# GD32Fx07R-dev-board.net
KiCad netlist of a schematic drawn in EAGLE
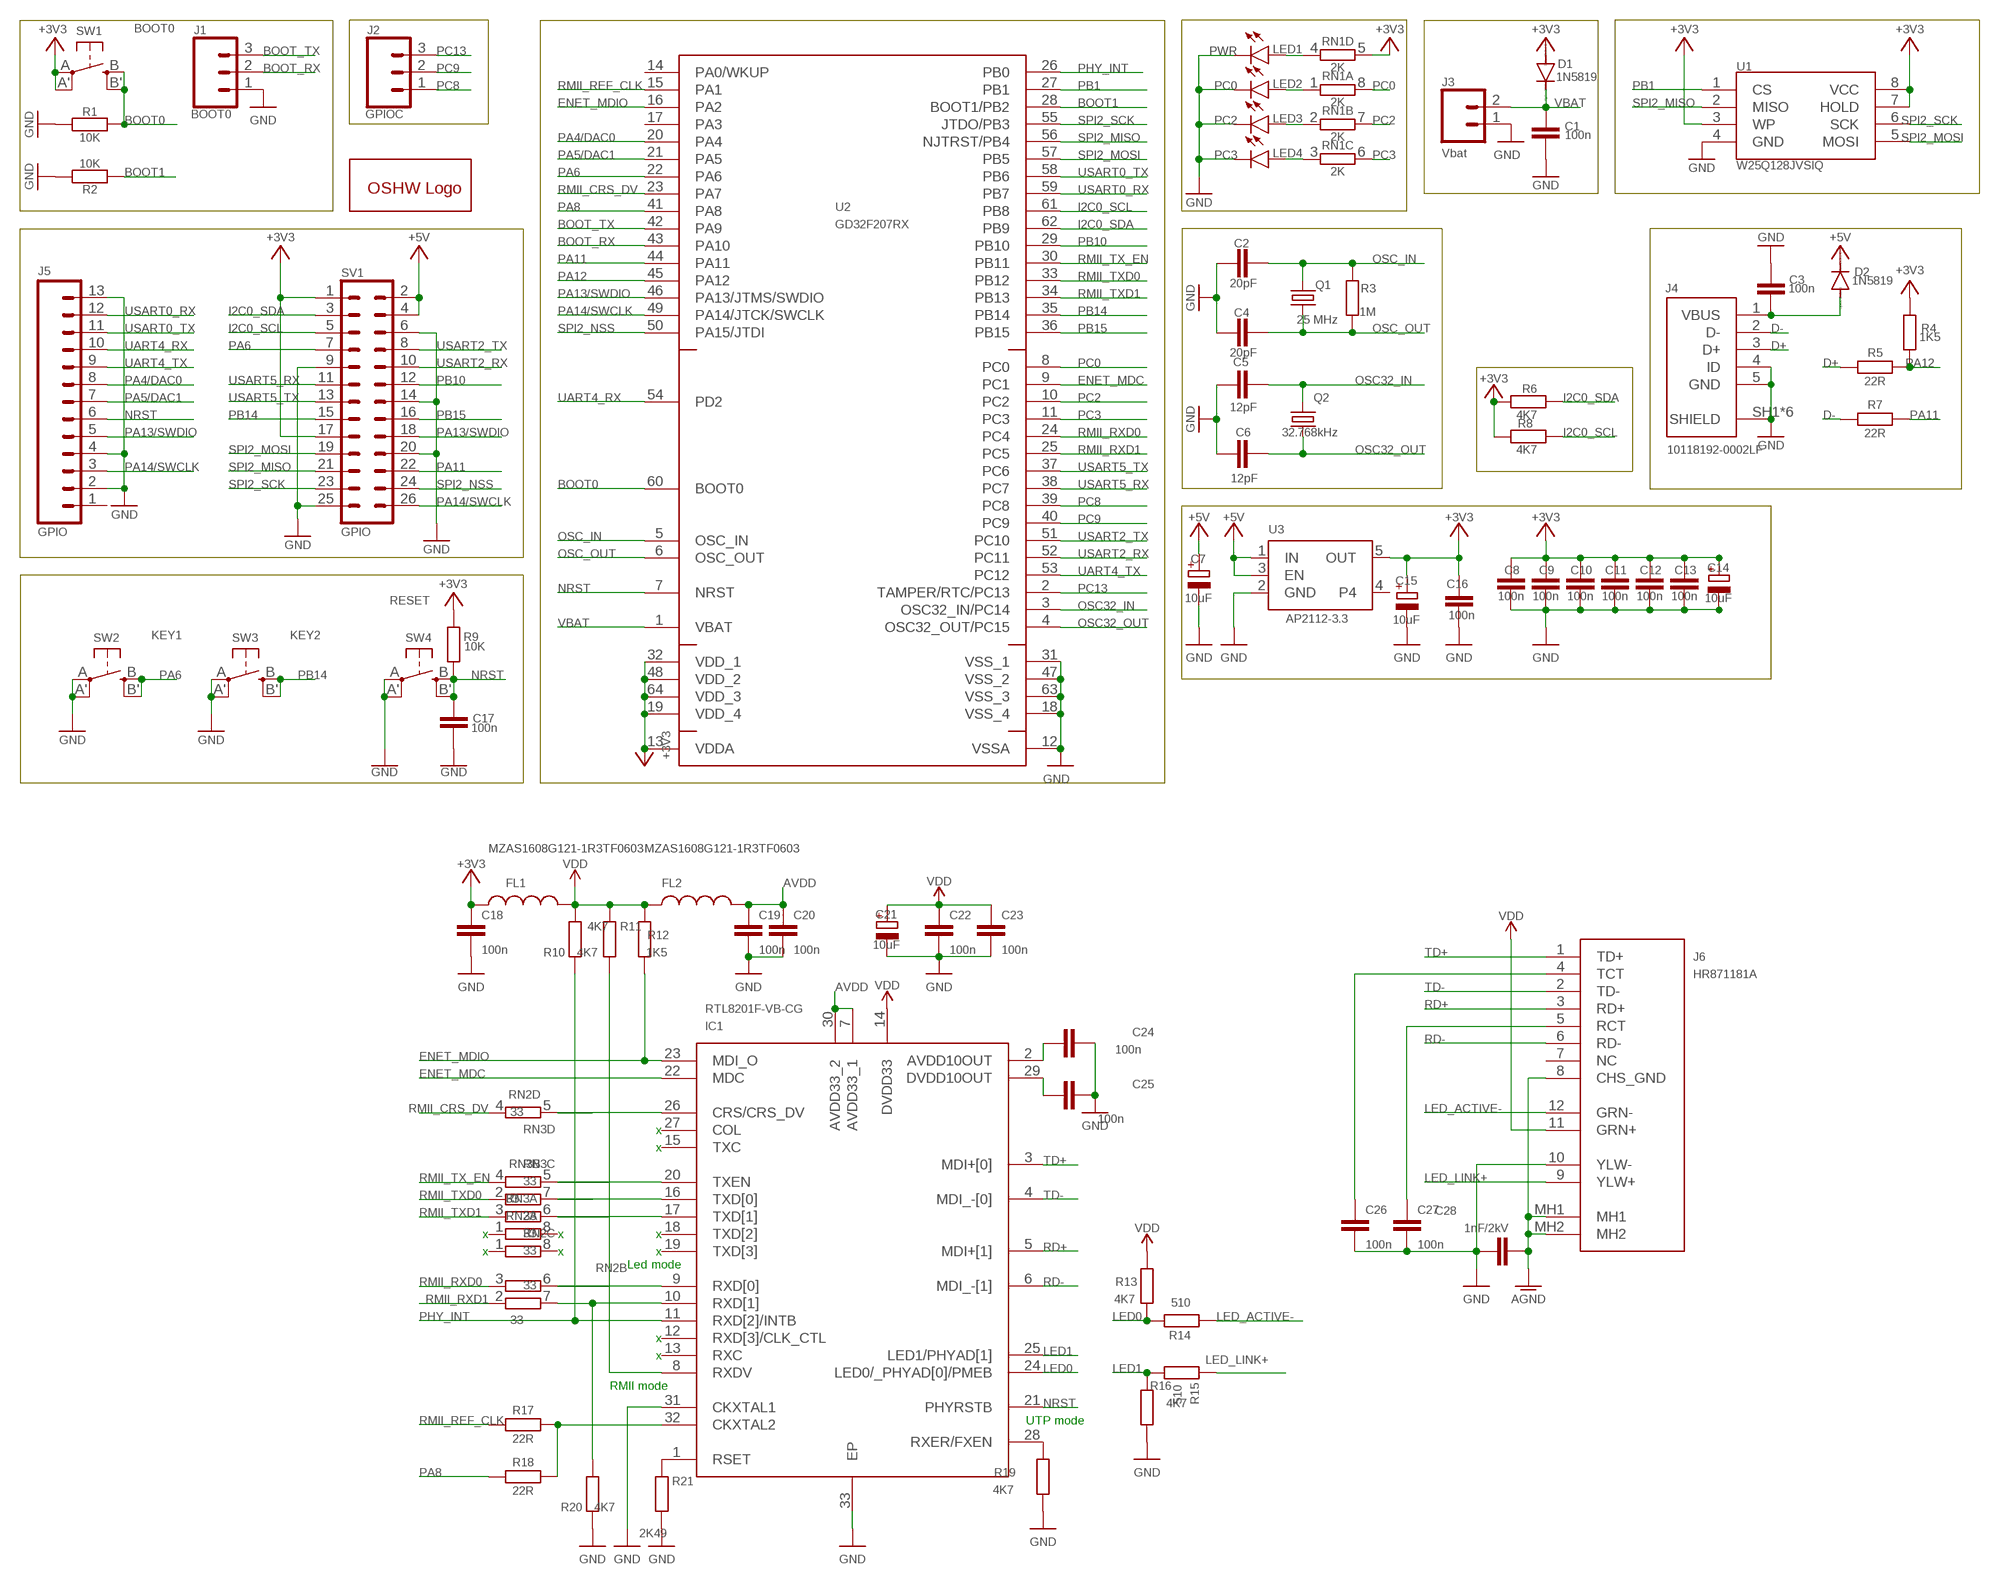
[diagram p0: schematic, sheet 1]

(export (version "E")
  (design (tool "Eeschema 10.0.6"))
  (components
    (comp (ref "C1")
      (value "100n")
      (footprint "eagle-import:C0603")
      (libsource (lib "eagle-import") (part "C-EUC0603"))
    )
    (comp (ref "C2")
      (value "20pF")
      (footprint "eagle-import:C0603")
      (libsource (lib "eagle-import") (part "C-EUC0603"))
    )
    (comp (ref "C3")
      (value "100n")
      (footprint "eagle-import:C0603")
      (libsource (lib "eagle-import") (part "C-EUC0603"))
    )
    (comp (ref "C4")
      (value "20pF")
      (footprint "eagle-import:C0603")
      (libsource (lib "eagle-import") (part "C-EUC0603"))
    )
    (comp (ref "C5")
      (value "12pF")
      (footprint "eagle-import:C0603")
      (libsource (lib "eagle-import") (part "C-EUC0603"))
    )
    (comp (ref "C6")
      (value "12pF")
      (footprint "eagle-import:C0603")
      (libsource (lib "eagle-import") (part "C-EUC0603"))
    )
    (comp (ref "C7")
      (value "10uF")
      (footprint "eagle-import:A_3216-18R")
      (libsource (lib "eagle-import") (part "CPOL-EUA/3216-18R"))
    )
    (comp (ref "C8")
      (value "100n")
      (footprint "eagle-import:C0603")
      (libsource (lib "eagle-import") (part "C-EUC0603"))
    )
    (comp (ref "C9")
      (value "100n")
      (footprint "eagle-import:C0603")
      (libsource (lib "eagle-import") (part "C-EUC0603"))
    )
    (comp (ref "C10")
      (value "100n")
      (footprint "eagle-import:C0603")
      (libsource (lib "eagle-import") (part "C-EUC0603"))
    )
    (comp (ref "C11")
      (value "100n")
      (footprint "eagle-import:C0603")
      (libsource (lib "eagle-import") (part "C-EUC0603"))
    )
    (comp (ref "C12")
      (value "100n")
      (footprint "eagle-import:C0603")
      (libsource (lib "eagle-import") (part "C-EUC0603"))
    )
    (comp (ref "C13")
      (value "100n")
      (footprint "eagle-import:C0603")
      (libsource (lib "eagle-import") (part "C-EUC0603"))
    )
    (comp (ref "C14")
      (value "10uF")
      (footprint "eagle-import:A_3216-18R")
      (libsource (lib "eagle-import") (part "CPOL-EUA/3216-18R"))
    )
    (comp (ref "C15")
      (value "10uF")
      (footprint "eagle-import:A_3216-18R")
      (libsource (lib "eagle-import") (part "CPOL-EUA/3216-18R"))
    )
    (comp (ref "C16")
      (value "100n")
      (footprint "eagle-import:C0603")
      (libsource (lib "eagle-import") (part "C-EUC0603"))
    )
    (comp (ref "C17")
      (value "100n")
      (footprint "eagle-import:C0603")
      (libsource (lib "eagle-import") (part "C-EUC0603"))
    )
    (comp (ref "C18")
      (value "100n")
      (footprint "eagle-import:C0603")
      (libsource (lib "eagle-import") (part "C-EUC0603"))
    )
    (comp (ref "C19")
      (value "100n")
      (footprint "eagle-import:C0603")
      (libsource (lib "eagle-import") (part "C-EUC0603"))
    )
    (comp (ref "C20")
      (value "100n")
      (footprint "eagle-import:C0603")
      (libsource (lib "eagle-import") (part "C-EUC0603"))
    )
    (comp (ref "C21")
      (value "10uF")
      (footprint "eagle-import:A_3216-18R")
      (libsource (lib "eagle-import") (part "CPOL-EUA/3216-18R"))
    )
    (comp (ref "C22")
      (value "100n")
      (footprint "eagle-import:C0603")
      (libsource (lib "eagle-import") (part "C-EUC0603"))
    )
    (comp (ref "C23")
      (value "100n")
      (footprint "eagle-import:C0603")
      (libsource (lib "eagle-import") (part "C-EUC0603"))
    )
    (comp (ref "C24")
      (value "100n")
      (footprint "eagle-import:C0603")
      (libsource (lib "eagle-import") (part "C-EUC0603"))
    )
    (comp (ref "C25")
      (value "100n")
      (footprint "eagle-import:C0603")
      (libsource (lib "eagle-import") (part "C-EUC0603"))
    )
    (comp (ref "C26")
      (value "100n")
      (footprint "eagle-import:C0603")
      (libsource (lib "eagle-import") (part "C-EUC0603"))
    )
    (comp (ref "C27")
      (value "100n")
      (footprint "eagle-import:C0603")
      (libsource (lib "eagle-import") (part "C-EUC0603"))
    )
    (comp (ref "C28")
      (value "1nF/2kV")
      (footprint "eagle-import:C1206")
      (fields (field (name "SPICEPREFIX") "C"))
      (libsource (lib "eagle-import") (part "C-EUC1206"))
    )
    (comp (ref "D1")
      (value "1N5819")
      (footprint "eagle-import:SOD323-R")
      (libsource (lib "eagle-import") (part "DIODE-SOD323-R"))
    )
    (comp (ref "D2")
      (value "1N5819")
      (footprint "eagle-import:SOD323-R")
      (libsource (lib "eagle-import") (part "DIODE-SOD323-R"))
    )
    (comp (ref "FL1")
      (value "MZAS1608G121-1R3TF0603")
      (footprint "eagle-import:0603")
      (libsource (lib "eagle-import") (part "MZAS1608G121-1R3TF0603"))
    )
    (comp (ref "FL2")
      (value "MZAS1608G121-1R3TF0603")
      (footprint "eagle-import:0603")
      (libsource (lib "eagle-import") (part "MZAS1608G121-1R3TF0603"))
    )
    (comp (ref "GOLD_ORB_SM1")
      (value "OSHWLOGOLOGO5MM")
      (footprint "eagle-import:OSHW_5MM")
      (libsource (lib "eagle-import") (part "OSHWLOGOLOGO5MM"))
    )
    (comp (ref "IC1")
      (value "RTL8201F-VB-CG")
      (footprint "eagle-import:QFN50P500X500X100-33N")
      (libsource (lib "eagle-import") (part "RTL8201F-VB-CG"))
    )
    (comp (ref "J1")
      (value "BOOT0")
      (footprint "eagle-import:1X03")
      (libsource (lib "eagle-import") (part "CONN_03"))
    )
    (comp (ref "J2")
      (value "GPIOC")
      (footprint "eagle-import:1X03")
      (libsource (lib "eagle-import") (part "CONN_03"))
    )
    (comp (ref "J3")
      (value "Vbat")
      (footprint "eagle-import:1X02_NO_SILK")
      (libsource (lib "eagle-import") (part "CONN_021X02_NO_SILK"))
    )
    (comp (ref "J4")
      (value "10118192-0002LF")
      (footprint "eagle-import:10118192-0002LF")
      (fields
        (field (name "DIGIKEY_PARTNO") "609-5379-2-ND")
        (field (name "MANUFACTURER") "Amphenol ICC (FCI)")
        (field (name "CREATED_BY") "PCBLayout.com")
      )
      (libsource (lib "eagle-import") (part "10118192-0002LF"))
    )
    (comp (ref "J5")
      (value "GPIO")
      (footprint "eagle-import:1X13")
      (libsource (lib "eagle-import") (part "CONN_13"))
    )
    (comp (ref "J6")
      (value "HR871181A")
      (footprint "eagle-import:HR871181A")
      (libsource (lib "eagle-import") (part "HR871181A"))
    )
    (comp (ref "LED1")
      (value "PWR")
      (footprint "eagle-import:CHIP-LED0603")
      (libsource (lib "eagle-import") (part "LEDCHIP-LED0603"))
    )
    (comp (ref "LED2")
      (value "PC0")
      (footprint "eagle-import:CHIP-LED0603")
      (libsource (lib "eagle-import") (part "LEDCHIP-LED0603"))
    )
    (comp (ref "LED3")
      (value "PC2")
      (footprint "eagle-import:CHIP-LED0603")
      (libsource (lib "eagle-import") (part "LEDCHIP-LED0603"))
    )
    (comp (ref "LED4")
      (value "PC3")
      (footprint "eagle-import:CHIP-LED0603")
      (libsource (lib "eagle-import") (part "LEDCHIP-LED0603"))
    )
    (comp (ref "Q1")
      (value "25 MHz")
      (footprint "eagle-import:CSM-7X-DU")
      (libsource (lib "eagle-import") (part "CSM-7X-DU"))
    )
    (comp (ref "Q2")
      (value "32.768kHz")
      (footprint "eagle-import:3.2X1.5")
      (libsource (lib "eagle-import") (part "KX-327-NHT"))
    )
    (comp (ref "R1")
      (value "10K")
      (footprint "eagle-import:R0603")
      (libsource (lib "eagle-import") (part "R-EU_R0603"))
    )
    (comp (ref "R2")
      (value "10K")
      (footprint "eagle-import:R0603")
      (libsource (lib "eagle-import") (part "R-EU_R0603"))
    )
    (comp (ref "R3")
      (value "1M")
      (footprint "eagle-import:R0603")
      (libsource (lib "eagle-import") (part "R-EU_R0603"))
    )
    (comp (ref "R4")
      (value "1K5")
      (footprint "eagle-import:R0603")
      (libsource (lib "eagle-import") (part "R-EU_R0603"))
    )
    (comp (ref "R5")
      (value "22R")
      (footprint "eagle-import:R0603")
      (libsource (lib "eagle-import") (part "R-EU_R0603"))
    )
    (comp (ref "R6")
      (value "4K7")
      (footprint "eagle-import:R0603")
      (libsource (lib "eagle-import") (part "R-EU_R0603"))
    )
    (comp (ref "R7")
      (value "22R")
      (footprint "eagle-import:R0603")
      (libsource (lib "eagle-import") (part "R-EU_R0603"))
    )
    (comp (ref "R8")
      (value "4K7")
      (footprint "eagle-import:R0603")
      (libsource (lib "eagle-import") (part "R-EU_R0603"))
    )
    (comp (ref "R9")
      (value "10K")
      (footprint "eagle-import:R0603")
      (libsource (lib "eagle-import") (part "R-EU_R0603"))
    )
    (comp (ref "R10")
      (value "4K7")
      (footprint "eagle-import:R0603")
      (libsource (lib "eagle-import") (part "R-EU_R0603"))
    )
    (comp (ref "R11")
      (value "4K7")
      (footprint "eagle-import:R0603")
      (libsource (lib "eagle-import") (part "R-EU_R0603"))
    )
    (comp (ref "R12")
      (value "1K5")
      (footprint "eagle-import:R0603")
      (libsource (lib "eagle-import") (part "R-EU_R0603"))
    )
    (comp (ref "R13")
      (value "4K7")
      (footprint "eagle-import:R0603")
      (libsource (lib "eagle-import") (part "R-EU_R0603"))
    )
    (comp (ref "R14")
      (value "510")
      (footprint "eagle-import:R0603")
      (libsource (lib "eagle-import") (part "R-EU_R0603"))
    )
    (comp (ref "R15")
      (value "510")
      (footprint "eagle-import:R0603")
      (libsource (lib "eagle-import") (part "R-EU_R0603"))
    )
    (comp (ref "R16")
      (value "4K7")
      (footprint "eagle-import:R0603")
      (libsource (lib "eagle-import") (part "R-EU_R0603"))
    )
    (comp (ref "R17")
      (value "22R")
      (footprint "eagle-import:R0603")
      (libsource (lib "eagle-import") (part "R-EU_R0603"))
    )
    (comp (ref "R18")
      (value "22R")
      (footprint "eagle-import:R0603")
      (libsource (lib "eagle-import") (part "R-EU_R0603"))
    )
    (comp (ref "R19")
      (value "4K7")
      (footprint "eagle-import:R0603")
      (libsource (lib "eagle-import") (part "R-EU_R0603"))
    )
    (comp (ref "R20")
      (value "4K7")
      (footprint "eagle-import:R0603")
      (libsource (lib "eagle-import") (part "R-EU_R0603"))
    )
    (comp (ref "R21")
      (value "2K49")
      (footprint "eagle-import:R0603")
      (libsource (lib "eagle-import") (part "R-EU_R0603"))
    )
    (comp (ref "RN1")
      (value "2K")
      (footprint "eagle-import:4X0402ARV341")
      (fields (field (name "JLCPCB") "C44891"))
      (libsource (lib "eagle-import") (part "4R-N0402ARV341"))
    )
    (comp (ref "RN2")
      (value "33")
      (footprint "eagle-import:4X0402ARV341")
      (fields (field (name "JLCPCB") "C25501"))
      (libsource (lib "eagle-import") (part "4R-N0402ARV341"))
    )
    (comp (ref "RN3")
      (value "33")
      (footprint "eagle-import:4X0402ARV341")
      (fields (field (name "JLCPCB") "C25501"))
      (libsource (lib "eagle-import") (part "4R-N0402ARV341"))
    )
    (comp (ref "SV1")
      (value "GPIO")
      (footprint "eagle-import:MA13-2")
      (libsource (lib "eagle-import") (part "GPIO-13-2"))
    )
    (comp (ref "SW1")
      (value "BOOT0")
      (footprint "eagle-import:EVQ-Q2")
      (libsource (lib "eagle-import") (part "SPST_TACT-EVQQ2"))
    )
    (comp (ref "SW2")
      (value "KEY1")
      (footprint "eagle-import:EVQ-Q2")
      (libsource (lib "eagle-import") (part "SPST_TACT-EVQQ2"))
    )
    (comp (ref "SW3")
      (value "KEY2")
      (footprint "eagle-import:EVQ-Q2")
      (libsource (lib "eagle-import") (part "SPST_TACT-EVQQ2"))
    )
    (comp (ref "SW4")
      (value "RESET")
      (footprint "eagle-import:EVQ-Q2")
      (libsource (lib "eagle-import") (part "SPST_TACT-EVQQ2"))
    )
    (comp (ref "U1")
      (value "W25Q128JVSIQ")
      (footprint "eagle-import:SO08-EIAJ")
      (libsource (lib "eagle-import") (part "SPI_FLASH-X25XXSMD1"))
    )
    (comp (ref "U2")
      (value "GD32F207RX")
      (footprint "eagle-import:LQFP64")
      (libsource (lib "eagle-import") (part "GD32F207RX"))
    )
    (comp (ref "U3")
      (value "AP2112-3.3")
      (footprint "eagle-import:SOT23-5")
      (fields (field (name "JLCPCB") "C51118"))
      (libsource (lib "eagle-import") (part "LDO"))
    )
  )
  (nets
    (net (code "1") (name "+3V3") (class "Default")
      (node (ref "C10") (pin "1") (pinfunction "1_1") (pintype "passive"))
      (node (ref "C11") (pin "1") (pinfunction "1_1") (pintype "passive"))
      (node (ref "C12") (pin "1") (pinfunction "1_1") (pintype "passive"))
      (node (ref "C13") (pin "1") (pinfunction "1_1") (pintype "passive"))
      (node (ref "C14") (pin "+") (pinfunction "+_+") (pintype "passive"))
      (node (ref "C15") (pin "+") (pinfunction "+_+") (pintype "passive"))
      (node (ref "C16") (pin "1") (pinfunction "1_1") (pintype "passive"))
      (node (ref "C18") (pin "1") (pinfunction "1_1") (pintype "passive"))
      (node (ref "C8") (pin "1") (pinfunction "1_1") (pintype "passive"))
      (node (ref "C9") (pin "1") (pinfunction "1_1") (pintype "passive"))
      (node (ref "D1") (pin "A") (pinfunction "A_A") (pintype "passive"))
      (node (ref "FL1") (pin "1") (pinfunction "1_1") (pintype "passive"))
      (node (ref "R4") (pin "2") (pinfunction "2_2") (pintype "passive"))
      (node (ref "R6") (pin "2") (pinfunction "2_2") (pintype "passive"))
      (node (ref "R8") (pin "2") (pinfunction "2_2") (pintype "passive"))
      (node (ref "R9") (pin "2") (pinfunction "2_2") (pintype "passive"))
      (node (ref "RN1") (pin "5") (pinfunction "2_5") (pintype "passive"))
      (node (ref "SV1") (pin "1") (pinfunction "1_1") (pintype "passive"))
      (node (ref "SV1") (pin "17") (pinfunction "17_17") (pintype "passive"))
      (node (ref "SW1") (pin "A") (pinfunction "P_A") (pintype "passive"))
      (node (ref "SW1") (pin "A'") (pinfunction "P1_A'") (pintype "passive"))
      (node (ref "U1") (pin "3") (pinfunction "WP_3") (pintype "bidirectional"))
      (node (ref "U1") (pin "7") (pinfunction "HOLD_7") (pintype "bidirectional"))
      (node (ref "U1") (pin "8") (pinfunction "VCC_8") (pintype "power_in"))
      (node (ref "U2") (pin "13") (pinfunction "VDDA_13") (pintype "power_in"))
      (node (ref "U2") (pin "19") (pinfunction "VDD_4_19") (pintype "power_in"))
      (node (ref "U2") (pin "32") (pinfunction "VDD_1_32") (pintype "power_in"))
      (node (ref "U2") (pin "48") (pinfunction "VDD_2_48") (pintype "power_in"))
      (node (ref "U2") (pin "64") (pinfunction "VDD_3_64") (pintype "power_in"))
      (node (ref "U3") (pin "5") (pinfunction "OUT_5") (pintype "power_in"))
    )
    (net (code "2") (name "+5V") (class "Default")
      (node (ref "C7") (pin "+") (pinfunction "+_+") (pintype "passive"))
      (node (ref "D2") (pin "C") (pinfunction "C_C") (pintype "passive"))
      (node (ref "SV1") (pin "2") (pinfunction "2_2") (pintype "passive"))
      (node (ref "SV1") (pin "4") (pinfunction "4_4") (pintype "passive"))
      (node (ref "U3") (pin "1") (pinfunction "IN_1") (pintype "power_in"))
      (node (ref "U3") (pin "3") (pinfunction "EN_3") (pintype "input"))
    )
    (net (code "3") (name "/AVDD") (class "Default")
      (node (ref "C19") (pin "1") (pinfunction "1_1") (pintype "passive"))
      (node (ref "C20") (pin "1") (pinfunction "1_1") (pintype "passive"))
      (node (ref "FL2") (pin "2") (pinfunction "2_2") (pintype "passive"))
      (node (ref "IC1") (pin "30") (pinfunction "AVDD33_2_30") (pintype "bidirectional"))
      (node (ref "IC1") (pin "7") (pinfunction "AVDD33_1_7") (pintype "bidirectional"))
    )
    (net (code "4") (name "/BOOT0") (class "Default")
      (node (ref "R1") (pin "2") (pinfunction "2_2") (pintype "passive"))
      (node (ref "SW1") (pin "B") (pinfunction "S_B") (pintype "passive"))
      (node (ref "SW1") (pin "B'") (pinfunction "S1_B'") (pintype "passive"))
      (node (ref "U2") (pin "60") (pinfunction "BOOT0_60") (pintype "bidirectional"))
    )
    (net (code "5") (name "/BOOT1") (class "Default")
      (node (ref "R2") (pin "1") (pinfunction "1_1") (pintype "passive"))
      (node (ref "U2") (pin "28") (pinfunction "BOOT1/PB2_28") (pintype "bidirectional"))
    )
    (net (code "6") (name "/BOOT_RX") (class "Default")
      (node (ref "J1") (pin "2") (pinfunction "2_2") (pintype "passive"))
      (node (ref "U2") (pin "43") (pinfunction "PA10_43") (pintype "bidirectional"))
    )
    (net (code "7") (name "/BOOT_TX") (class "Default")
      (node (ref "J1") (pin "3") (pinfunction "3_3") (pintype "passive"))
      (node (ref "U2") (pin "42") (pinfunction "PA9_42") (pintype "bidirectional"))
    )
    (net (code "8") (name "/D+") (class "Default")
      (node (ref "J4") (pin "3") (pinfunction "D+_3") (pintype "passive"))
      (node (ref "R5") (pin "1") (pinfunction "1_1") (pintype "passive"))
    )
    (net (code "9") (name "/D-") (class "Default")
      (node (ref "J4") (pin "2") (pinfunction "D-_2") (pintype "passive"))
      (node (ref "R7") (pin "1") (pinfunction "1_1") (pintype "passive"))
    )
    (net (code "10") (name "/ENET_MDC") (class "Default")
      (node (ref "IC1") (pin "22") (pinfunction "MDC_22") (pintype "bidirectional"))
      (node (ref "U2") (pin "9") (pinfunction "PC1_9") (pintype "bidirectional"))
    )
    (net (code "11") (name "/ENET_MDIO") (class "Default")
      (node (ref "IC1") (pin "23") (pinfunction "MDI_O_23") (pintype "bidirectional"))
      (node (ref "R12") (pin "1") (pinfunction "1_1") (pintype "passive"))
      (node (ref "U2") (pin "16") (pinfunction "PA2_16") (pintype "bidirectional"))
    )
    (net (code "12") (name "/I2C0_SCL") (class "Default")
      (node (ref "R8") (pin "1") (pinfunction "1_1") (pintype "passive"))
      (node (ref "SV1") (pin "5") (pinfunction "5_5") (pintype "passive"))
      (node (ref "U2") (pin "61") (pinfunction "PB8_61") (pintype "bidirectional"))
    )
    (net (code "13") (name "/I2C0_SDA") (class "Default")
      (node (ref "R6") (pin "1") (pinfunction "1_1") (pintype "passive"))
      (node (ref "SV1") (pin "3") (pinfunction "3_3") (pintype "passive"))
      (node (ref "U2") (pin "62") (pinfunction "PB9_62") (pintype "bidirectional"))
    )
    (net (code "14") (name "/LED0") (class "Default")
      (node (ref "IC1") (pin "24") (pinfunction "LED0/_PHYAD[0]/PMEB_24") (pintype "bidirectional"))
      (node (ref "R13") (pin "1") (pinfunction "1_1") (pintype "passive"))
      (node (ref "R14") (pin "2") (pinfunction "2_2") (pintype "passive"))
    )
    (net (code "15") (name "/LED1") (class "Default")
      (node (ref "IC1") (pin "25") (pinfunction "LED1/PHYAD[1]_25") (pintype "bidirectional"))
      (node (ref "R15") (pin "2") (pinfunction "2_2") (pintype "passive"))
      (node (ref "R16") (pin "2") (pinfunction "2_2") (pintype "passive"))
    )
    (net (code "16") (name "/LED_ACTIVE-") (class "Default")
      (node (ref "J6") (pin "12") (pinfunction "GRN-_12") (pintype "bidirectional"))
      (node (ref "R14") (pin "1") (pinfunction "1_1") (pintype "passive"))
    )
    (net (code "17") (name "/LED_LINK+") (class "Default")
      (node (ref "J6") (pin "9") (pinfunction "YLW+_9") (pintype "bidirectional"))
      (node (ref "R15") (pin "1") (pinfunction "1_1") (pintype "passive"))
    )
    (net (code "18") (name "/NRST") (class "Default")
      (node (ref "C17") (pin "1") (pinfunction "1_1") (pintype "passive"))
      (node (ref "IC1") (pin "21") (pinfunction "PHYRSTB_21") (pintype "bidirectional"))
      (node (ref "J5") (pin "6") (pinfunction "6_6") (pintype "passive"))
      (node (ref "R9") (pin "1") (pinfunction "1_1") (pintype "passive"))
      (node (ref "SW4") (pin "B") (pinfunction "S_B") (pintype "passive"))
      (node (ref "SW4") (pin "B'") (pinfunction "S1_B'") (pintype "passive"))
      (node (ref "U2") (pin "7") (pinfunction "NRST_7") (pintype "power_in"))
    )
    (net (code "19") (name "/OSC32_IN") (class "Default")
      (node (ref "C5") (pin "2") (pinfunction "2_2") (pintype "passive"))
      (node (ref "Q2") (pin "2") (pinfunction "2_2") (pintype "passive"))
      (node (ref "U2") (pin "3") (pinfunction "OSC32_IN/PC14_3") (pintype "bidirectional"))
    )
    (net (code "20") (name "/OSC32_OUT") (class "Default")
      (node (ref "C6") (pin "2") (pinfunction "2_2") (pintype "passive"))
      (node (ref "Q2") (pin "1") (pinfunction "1_1") (pintype "passive"))
      (node (ref "U2") (pin "4") (pinfunction "OSC32_OUT/PC15_4") (pintype "bidirectional"))
    )
    (net (code "21") (name "/OSC_IN") (class "Default")
      (node (ref "C2") (pin "2") (pinfunction "2_2") (pintype "passive"))
      (node (ref "Q1") (pin "2") (pinfunction "2_2") (pintype "passive"))
      (node (ref "R3") (pin "1") (pinfunction "1_1") (pintype "passive"))
      (node (ref "U2") (pin "5") (pinfunction "OSC_IN_5") (pintype "bidirectional"))
    )
    (net (code "22") (name "/OSC_OUT") (class "Default")
      (node (ref "C4") (pin "2") (pinfunction "2_2") (pintype "passive"))
      (node (ref "Q1") (pin "1") (pinfunction "1_1") (pintype "passive"))
      (node (ref "R3") (pin "2") (pinfunction "2_2") (pintype "passive"))
      (node (ref "U2") (pin "6") (pinfunction "OSC_OUT_6") (pintype "bidirectional"))
    )
    (net (code "23") (name "/PA4{slash}DAC0") (class "Default")
      (node (ref "J5") (pin "8") (pinfunction "8_8") (pintype "passive"))
      (node (ref "U2") (pin "20") (pinfunction "PA4_20") (pintype "bidirectional"))
    )
    (net (code "24") (name "/PA5{slash}DAC1") (class "Default")
      (node (ref "J5") (pin "7") (pinfunction "7_7") (pintype "passive"))
      (node (ref "U2") (pin "21") (pinfunction "PA5_21") (pintype "bidirectional"))
    )
    (net (code "25") (name "/PA6") (class "Default")
      (node (ref "SV1") (pin "7") (pinfunction "7_7") (pintype "passive"))
      (node (ref "SW2") (pin "B") (pinfunction "S_B") (pintype "passive"))
      (node (ref "SW2") (pin "B'") (pinfunction "S1_B'") (pintype "passive"))
      (node (ref "U2") (pin "22") (pinfunction "PA6_22") (pintype "bidirectional"))
    )
    (net (code "26") (name "/PA8") (class "Default")
      (node (ref "R18") (pin "1") (pinfunction "1_1") (pintype "passive"))
      (node (ref "U2") (pin "41") (pinfunction "PA8_41") (pintype "bidirectional"))
    )
    (net (code "27") (name "/PA11") (class "Default")
      (node (ref "R7") (pin "2") (pinfunction "2_2") (pintype "passive"))
      (node (ref "SV1") (pin "22") (pinfunction "22_22") (pintype "passive"))
      (node (ref "U2") (pin "44") (pinfunction "PA11_44") (pintype "bidirectional"))
    )
    (net (code "28") (name "/PA12") (class "Default")
      (node (ref "R4") (pin "1") (pinfunction "1_1") (pintype "passive"))
      (node (ref "R5") (pin "2") (pinfunction "2_2") (pintype "passive"))
      (node (ref "U2") (pin "45") (pinfunction "PA12_45") (pintype "bidirectional"))
    )
    (net (code "29") (name "/PA13{slash}SWDIO") (class "Default")
      (node (ref "J5") (pin "5") (pinfunction "5_5") (pintype "passive"))
      (node (ref "SV1") (pin "18") (pinfunction "18_18") (pintype "passive"))
      (node (ref "U2") (pin "46") (pinfunction "PA13/JTMS/SWDIO_46") (pintype "bidirectional"))
    )
    (net (code "30") (name "/PA14{slash}SWCLK") (class "Default")
      (node (ref "J5") (pin "3") (pinfunction "3_3") (pintype "passive"))
      (node (ref "SV1") (pin "26") (pinfunction "26_26") (pintype "passive"))
      (node (ref "U2") (pin "49") (pinfunction "PA14/JTCK/SWCLK_49") (pintype "bidirectional"))
    )
    (net (code "31") (name "/PB1") (class "Default")
      (node (ref "U1") (pin "1") (pinfunction "CS_1") (pintype "bidirectional"))
      (node (ref "U2") (pin "27") (pinfunction "PB1_27") (pintype "bidirectional"))
    )
    (net (code "32") (name "/PB10") (class "Default")
      (node (ref "SV1") (pin "12") (pinfunction "12_12") (pintype "passive"))
      (node (ref "U2") (pin "29") (pinfunction "PB10_29") (pintype "bidirectional"))
    )
    (net (code "33") (name "/PB14") (class "Default")
      (node (ref "SV1") (pin "15") (pinfunction "15_15") (pintype "passive"))
      (node (ref "SW3") (pin "B") (pinfunction "S_B") (pintype "passive"))
      (node (ref "SW3") (pin "B'") (pinfunction "S1_B'") (pintype "passive"))
      (node (ref "U2") (pin "35") (pinfunction "PB14_35") (pintype "bidirectional"))
    )
    (net (code "34") (name "/PB15") (class "Default")
      (node (ref "SV1") (pin "16") (pinfunction "16_16") (pintype "passive"))
      (node (ref "U2") (pin "36") (pinfunction "PB15_36") (pintype "bidirectional"))
    )
    (net (code "35") (name "/PC0") (class "Default")
      (node (ref "RN1") (pin "8") (pinfunction "2_8") (pintype "passive"))
      (node (ref "U2") (pin "8") (pinfunction "PC0_8") (pintype "bidirectional"))
    )
    (net (code "36") (name "/PC2") (class "Default")
      (node (ref "RN1") (pin "7") (pinfunction "2_7") (pintype "passive"))
      (node (ref "U2") (pin "10") (pinfunction "PC2_10") (pintype "bidirectional"))
    )
    (net (code "37") (name "/PC3") (class "Default")
      (node (ref "RN1") (pin "6") (pinfunction "2_6") (pintype "passive"))
      (node (ref "U2") (pin "11") (pinfunction "PC3_11") (pintype "bidirectional"))
    )
    (net (code "38") (name "/PC8") (class "Default")
      (node (ref "J2") (pin "1") (pinfunction "1_1") (pintype "passive"))
      (node (ref "U2") (pin "39") (pinfunction "PC8_39") (pintype "bidirectional"))
    )
    (net (code "39") (name "/PC9") (class "Default")
      (node (ref "J2") (pin "2") (pinfunction "2_2") (pintype "passive"))
      (node (ref "U2") (pin "40") (pinfunction "PC9_40") (pintype "bidirectional"))
    )
    (net (code "40") (name "/PC13") (class "Default")
      (node (ref "J2") (pin "3") (pinfunction "3_3") (pintype "passive"))
      (node (ref "U2") (pin "2") (pinfunction "TAMPER/RTC/PC13_2") (pintype "bidirectional"))
    )
    (net (code "41") (name "/PHY_INT") (class "Default")
      (node (ref "IC1") (pin "11") (pinfunction "RXD[2]/INTB_11") (pintype "bidirectional"))
      (node (ref "R10") (pin "1") (pinfunction "1_1") (pintype "passive"))
      (node (ref "U2") (pin "26") (pinfunction "PB0_26") (pintype "bidirectional"))
    )
    (net (code "42") (name "/RD+") (class "Default")
      (node (ref "IC1") (pin "5") (pinfunction "MDI+[1]_5") (pintype "bidirectional"))
      (node (ref "J6") (pin "3") (pinfunction "RD+_3") (pintype "bidirectional"))
    )
    (net (code "43") (name "/RD-") (class "Default")
      (node (ref "IC1") (pin "6") (pinfunction "MDI_-[1]_6") (pintype "bidirectional"))
      (node (ref "J6") (pin "6") (pinfunction "RD-_6") (pintype "bidirectional"))
    )
    (net (code "44") (name "/RMII_CRS_DV") (class "Default")
      (node (ref "RN2") (pin "4") (pinfunction "1_4") (pintype "passive"))
      (node (ref "U2") (pin "23") (pinfunction "PA7_23") (pintype "bidirectional"))
    )
    (net (code "45") (name "/RMII_REF_CLK") (class "Default")
      (node (ref "R17") (pin "1") (pinfunction "1_1") (pintype "passive"))
      (node (ref "U2") (pin "15") (pinfunction "PA1_15") (pintype "bidirectional"))
    )
    (net (code "46") (name "/RMII_RXD0") (class "Default")
      (node (ref "RN2") (pin "3") (pinfunction "1_3") (pintype "passive"))
      (node (ref "U2") (pin "24") (pinfunction "PC4_24") (pintype "bidirectional"))
    )
    (net (code "47") (name "/RMII_RXD1") (class "Default")
      (node (ref "RN2") (pin "2") (pinfunction "1_2") (pintype "passive"))
      (node (ref "U2") (pin "25") (pinfunction "PC5_25") (pintype "bidirectional"))
    )
    (net (code "48") (name "/RMII_TXD0") (class "Default")
      (node (ref "RN3") (pin "2") (pinfunction "1_2") (pintype "passive"))
      (node (ref "U2") (pin "33") (pinfunction "PB12_33") (pintype "bidirectional"))
    )
    (net (code "49") (name "/RMII_TXD1") (class "Default")
      (node (ref "RN3") (pin "3") (pinfunction "1_3") (pintype "passive"))
      (node (ref "U2") (pin "34") (pinfunction "PB13_34") (pintype "bidirectional"))
    )
    (net (code "50") (name "/RMII_TX_EN") (class "Default")
      (node (ref "RN3") (pin "4") (pinfunction "1_4") (pintype "passive"))
      (node (ref "U2") (pin "30") (pinfunction "PB11_30") (pintype "bidirectional"))
    )
    (net (code "51") (name "/SPI2_MISO") (class "Default")
      (node (ref "SV1") (pin "21") (pinfunction "21_21") (pintype "passive"))
      (node (ref "U1") (pin "2") (pinfunction "MISO_2") (pintype "bidirectional"))
      (node (ref "U2") (pin "56") (pinfunction "NJTRST/PB4_56") (pintype "bidirectional"))
    )
    (net (code "52") (name "/SPI2_MOSI") (class "Default")
      (node (ref "SV1") (pin "19") (pinfunction "19_19") (pintype "passive"))
      (node (ref "U1") (pin "5") (pinfunction "MOSI_5") (pintype "bidirectional"))
      (node (ref "U2") (pin "57") (pinfunction "PB5_57") (pintype "bidirectional"))
    )
    (net (code "53") (name "/SPI2_NSS") (class "Default")
      (node (ref "SV1") (pin "24") (pinfunction "24_24") (pintype "passive"))
      (node (ref "U2") (pin "50") (pinfunction "PA15/JTDI_50") (pintype "bidirectional"))
    )
    (net (code "54") (name "/SPI2_SCK") (class "Default")
      (node (ref "SV1") (pin "23") (pinfunction "23_23") (pintype "passive"))
      (node (ref "U1") (pin "6") (pinfunction "SCK_6") (pintype "bidirectional"))
      (node (ref "U2") (pin "55") (pinfunction "JTDO/PB3_55") (pintype "bidirectional"))
    )
    (net (code "55") (name "/TD+") (class "Default")
      (node (ref "IC1") (pin "3") (pinfunction "MDI+[0]_3") (pintype "bidirectional"))
      (node (ref "J6") (pin "1") (pinfunction "TD+_1") (pintype "bidirectional"))
    )
    (net (code "56") (name "/TD-") (class "Default")
      (node (ref "IC1") (pin "4") (pinfunction "MDI_-[0]_4") (pintype "bidirectional"))
      (node (ref "J6") (pin "2") (pinfunction "TD-_2") (pintype "bidirectional"))
    )
    (net (code "57") (name "/UART4_RX") (class "Default")
      (node (ref "J5") (pin "10") (pinfunction "10_10") (pintype "passive"))
      (node (ref "U2") (pin "54") (pinfunction "PD2_54") (pintype "bidirectional"))
    )
    (net (code "58") (name "/UART4_TX") (class "Default")
      (node (ref "J5") (pin "9") (pinfunction "9_9") (pintype "passive"))
      (node (ref "U2") (pin "53") (pinfunction "PC12_53") (pintype "bidirectional"))
    )
    (net (code "59") (name "/USART0_RX") (class "Default")
      (node (ref "J5") (pin "12") (pinfunction "12_12") (pintype "passive"))
      (node (ref "U2") (pin "59") (pinfunction "PB7_59") (pintype "bidirectional"))
    )
    (net (code "60") (name "/USART0_TX") (class "Default")
      (node (ref "J5") (pin "11") (pinfunction "11_11") (pintype "passive"))
      (node (ref "U2") (pin "58") (pinfunction "PB6_58") (pintype "bidirectional"))
    )
    (net (code "61") (name "/USART2_RX") (class "Default")
      (node (ref "SV1") (pin "10") (pinfunction "10_10") (pintype "passive"))
      (node (ref "U2") (pin "52") (pinfunction "PC11_52") (pintype "bidirectional"))
    )
    (net (code "62") (name "/USART2_TX") (class "Default")
      (node (ref "SV1") (pin "8") (pinfunction "8_8") (pintype "passive"))
      (node (ref "U2") (pin "51") (pinfunction "PC10_51") (pintype "bidirectional"))
    )
    (net (code "63") (name "/USART5_RX") (class "Default")
      (node (ref "SV1") (pin "11") (pinfunction "11_11") (pintype "passive"))
      (node (ref "U2") (pin "38") (pinfunction "PC7_38") (pintype "bidirectional"))
    )
    (net (code "64") (name "/USART5_TX") (class "Default")
      (node (ref "SV1") (pin "13") (pinfunction "13_13") (pintype "passive"))
      (node (ref "U2") (pin "37") (pinfunction "PC6_37") (pintype "bidirectional"))
    )
    (net (code "65") (name "/VBAT") (class "Default")
      (node (ref "C1") (pin "1") (pinfunction "1_1") (pintype "passive"))
      (node (ref "D1") (pin "C") (pinfunction "C_C") (pintype "passive"))
      (node (ref "J3") (pin "2") (pinfunction "2_2") (pintype "passive"))
      (node (ref "U2") (pin "1") (pinfunction "VBAT_1") (pintype "power_in"))
    )
    (net (code "66") (name "AGND") (class "Default")
      (node (ref "C28") (pin "2") (pinfunction "2_2") (pintype "passive"))
      (node (ref "J6") (pin "8") (pinfunction "CHS_GND_8") (pintype "bidirectional"))
      (node (ref "J6") (pin "MH1") (pinfunction "MH1_MH1") (pintype "bidirectional"))
      (node (ref "J6") (pin "MH2") (pinfunction "MH2_MH2") (pintype "bidirectional"))
    )
    (net (code "67") (name "GND") (class "Default")
      (node (ref "C1") (pin "2") (pinfunction "2_2") (pintype "passive"))
      (node (ref "C10") (pin "2") (pinfunction "2_2") (pintype "passive"))
      (node (ref "C11") (pin "2") (pinfunction "2_2") (pintype "passive"))
      (node (ref "C12") (pin "2") (pinfunction "2_2") (pintype "passive"))
      (node (ref "C13") (pin "2") (pinfunction "2_2") (pintype "passive"))
      (node (ref "C14") (pin "-") (pinfunction "-_-") (pintype "passive"))
      (node (ref "C15") (pin "-") (pinfunction "-_-") (pintype "passive"))
      (node (ref "C16") (pin "2") (pinfunction "2_2") (pintype "passive"))
      (node (ref "C17") (pin "2") (pinfunction "2_2") (pintype "passive"))
      (node (ref "C18") (pin "2") (pinfunction "2_2") (pintype "passive"))
      (node (ref "C19") (pin "2") (pinfunction "2_2") (pintype "passive"))
      (node (ref "C2") (pin "1") (pinfunction "1_1") (pintype "passive"))
      (node (ref "C20") (pin "2") (pinfunction "2_2") (pintype "passive"))
      (node (ref "C21") (pin "-") (pinfunction "-_-") (pintype "passive"))
      (node (ref "C22") (pin "2") (pinfunction "2_2") (pintype "passive"))
      (node (ref "C23") (pin "2") (pinfunction "2_2") (pintype "passive"))
      (node (ref "C24") (pin "1") (pinfunction "1_1") (pintype "passive"))
      (node (ref "C25") (pin "1") (pinfunction "1_1") (pintype "passive"))
      (node (ref "C26") (pin "2") (pinfunction "2_2") (pintype "passive"))
      (node (ref "C27") (pin "2") (pinfunction "2_2") (pintype "passive"))
      (node (ref "C28") (pin "1") (pinfunction "1_1") (pintype "passive"))
      (node (ref "C3") (pin "1") (pinfunction "1_1") (pintype "passive"))
      (node (ref "C4") (pin "1") (pinfunction "1_1") (pintype "passive"))
      (node (ref "C5") (pin "1") (pinfunction "1_1") (pintype "passive"))
      (node (ref "C6") (pin "1") (pinfunction "1_1") (pintype "passive"))
      (node (ref "C7") (pin "-") (pinfunction "-_-") (pintype "passive"))
      (node (ref "C8") (pin "2") (pinfunction "2_2") (pintype "passive"))
      (node (ref "C9") (pin "2") (pinfunction "2_2") (pintype "passive"))
      (node (ref "IC1") (pin "31") (pinfunction "CKXTAL1_31") (pintype "bidirectional"))
      (node (ref "IC1") (pin "33") (pinfunction "EP_33") (pintype "bidirectional"))
      (node (ref "J1") (pin "1") (pinfunction "1_1") (pintype "passive"))
      (node (ref "J3") (pin "1") (pinfunction "1_1") (pintype "passive"))
      (node (ref "J4") (pin "4") (pinfunction "ID_4") (pintype "passive"))
      (node (ref "J4") (pin "5") (pinfunction "GND_5") (pintype "passive"))
      (node (ref "J4") (pin "SH1") (pinfunction "SHIELD_SH1") (pintype "power_in"))
      (node (ref "J4") (pin "SH2") (pinfunction "SHIELD_SH2") (pintype "power_in"))
      (node (ref "J4") (pin "SH3") (pinfunction "SHIELD_SH3") (pintype "power_in"))
      (node (ref "J4") (pin "SH4") (pinfunction "SHIELD_SH4") (pintype "power_in"))
      (node (ref "J4") (pin "SH5") (pinfunction "SHIELD_SH5") (pintype "power_in"))
      (node (ref "J4") (pin "SH6") (pinfunction "SHIELD_SH6") (pintype "power_in"))
      (node (ref "J5") (pin "13") (pinfunction "13_13") (pintype "passive"))
      (node (ref "J5") (pin "2") (pinfunction "2_2") (pintype "passive"))
      (node (ref "J5") (pin "4") (pinfunction "4_4") (pintype "passive"))
      (node (ref "J6") (pin "10") (pinfunction "YLW-_10") (pintype "bidirectional"))
      (node (ref "LED1") (pin "C") (pinfunction "C_C") (pintype "passive"))
      (node (ref "LED2") (pin "C") (pinfunction "C_C") (pintype "passive"))
      (node (ref "LED3") (pin "C") (pinfunction "C_C") (pintype "passive"))
      (node (ref "LED4") (pin "C") (pinfunction "C_C") (pintype "passive"))
      (node (ref "R1") (pin "1") (pinfunction "1_1") (pintype "passive"))
      (node (ref "R16") (pin "1") (pinfunction "1_1") (pintype "passive"))
      (node (ref "R19") (pin "1") (pinfunction "1_1") (pintype "passive"))
      (node (ref "R2") (pin "2") (pinfunction "2_2") (pintype "passive"))
      (node (ref "R20") (pin "1") (pinfunction "1_1") (pintype "passive"))
      (node (ref "R21") (pin "2") (pinfunction "2_2") (pintype "passive"))
      (node (ref "SV1") (pin "14") (pinfunction "14_14") (pintype "passive"))
      (node (ref "SV1") (pin "20") (pinfunction "20_20") (pintype "passive"))
      (node (ref "SV1") (pin "25") (pinfunction "25_25") (pintype "passive"))
      (node (ref "SV1") (pin "6") (pinfunction "6_6") (pintype "passive"))
      (node (ref "SV1") (pin "9") (pinfunction "9_9") (pintype "passive"))
      (node (ref "SW2") (pin "A") (pinfunction "P_A") (pintype "passive"))
      (node (ref "SW2") (pin "A'") (pinfunction "P1_A'") (pintype "passive"))
      (node (ref "SW3") (pin "A") (pinfunction "P_A") (pintype "passive"))
      (node (ref "SW3") (pin "A'") (pinfunction "P1_A'") (pintype "passive"))
      (node (ref "SW4") (pin "A") (pinfunction "P_A") (pintype "passive"))
      (node (ref "SW4") (pin "A'") (pinfunction "P1_A'") (pintype "passive"))
      (node (ref "U1") (pin "4") (pinfunction "GND_4") (pintype "power_in"))
      (node (ref "U2") (pin "12") (pinfunction "VSSA_12") (pintype "power_in"))
      (node (ref "U2") (pin "18") (pinfunction "VSS_4_18") (pintype "power_in"))
      (node (ref "U2") (pin "31") (pinfunction "VSS_1_31") (pintype "power_in"))
      (node (ref "U2") (pin "47") (pinfunction "VSS_2_47") (pintype "power_in"))
      (node (ref "U2") (pin "63") (pinfunction "VSS_3_63") (pintype "power_in"))
      (node (ref "U3") (pin "2") (pinfunction "GND_2") (pintype "power_in"))
    )
    (net (code "68") (name "Net-(IC1-AVDD10OUT)") (class "Default")
      (node (ref "C24") (pin "2") (pinfunction "2_2") (pintype "passive"))
      (node (ref "IC1") (pin "2") (pinfunction "AVDD10OUT_2") (pintype "bidirectional"))
    )
    (net (code "69") (name "Net-(IC1-CKXTAL2)") (class "Default")
      (node (ref "IC1") (pin "32") (pinfunction "CKXTAL2_32") (pintype "bidirectional"))
      (node (ref "R17") (pin "2") (pinfunction "2_2") (pintype "passive"))
      (node (ref "R18") (pin "2") (pinfunction "2_2") (pintype "passive"))
    )
    (net (code "70") (name "Net-(IC1-CRS{slash}CRS_DV)") (class "Default")
      (node (ref "IC1") (pin "26") (pinfunction "CRS/CRS_DV_26") (pintype "bidirectional"))
      (node (ref "RN2") (pin "5") (pinfunction "2_5") (pintype "passive"))
    )
    (net (code "71") (name "Net-(IC1-DVDD10OUT)") (class "Default")
      (node (ref "C25") (pin "2") (pinfunction "2_2") (pintype "passive"))
      (node (ref "IC1") (pin "29") (pinfunction "DVDD10OUT_29") (pintype "bidirectional"))
    )
    (net (code "72") (name "Net-(IC1-RSET)") (class "Default")
      (node (ref "IC1") (pin "1") (pinfunction "RSET_1") (pintype "bidirectional"))
      (node (ref "R21") (pin "1") (pinfunction "1_1") (pintype "passive"))
    )
    (net (code "73") (name "Net-(IC1-RXDV)") (class "Default")
      (node (ref "IC1") (pin "8") (pinfunction "RXDV_8") (pintype "bidirectional"))
      (node (ref "R11") (pin "2") (pinfunction "2_2") (pintype "passive"))
    )
    (net (code "74") (name "Net-(IC1-RXD[0])") (class "Default")
      (node (ref "IC1") (pin "9") (pinfunction "RXD[0]_9") (pintype "bidirectional"))
      (node (ref "RN2") (pin "6") (pinfunction "2_6") (pintype "passive"))
    )
    (net (code "75") (name "Net-(IC1-RXD[1])") (class "Default")
      (node (ref "IC1") (pin "10") (pinfunction "RXD[1]_10") (pintype "bidirectional"))
      (node (ref "R20") (pin "2") (pinfunction "2_2") (pintype "passive"))
      (node (ref "RN2") (pin "7") (pinfunction "2_7") (pintype "passive"))
    )
    (net (code "76") (name "Net-(IC1-RXER{slash}FXEN)") (class "Default")
      (node (ref "IC1") (pin "28") (pinfunction "RXER/FXEN_28") (pintype "bidirectional"))
      (node (ref "R19") (pin "2") (pinfunction "2_2") (pintype "passive"))
    )
    (net (code "77") (name "Net-(IC1-TXD[0])") (class "Default")
      (node (ref "IC1") (pin "16") (pinfunction "TXD[0]_16") (pintype "bidirectional"))
      (node (ref "RN3") (pin "7") (pinfunction "2_7") (pintype "passive"))
    )
    (net (code "78") (name "Net-(IC1-TXD[1])") (class "Default")
      (node (ref "IC1") (pin "17") (pinfunction "TXD[1]_17") (pintype "bidirectional"))
      (node (ref "RN3") (pin "6") (pinfunction "2_6") (pintype "passive"))
    )
    (net (code "79") (name "Net-(IC1-TXEN)") (class "Default")
      (node (ref "IC1") (pin "20") (pinfunction "TXEN_20") (pintype "bidirectional"))
      (node (ref "RN3") (pin "5") (pinfunction "2_5") (pintype "passive"))
    )
    (net (code "80") (name "Net-(J4-VBUS)") (class "Default")
      (node (ref "C3") (pin "2") (pinfunction "2_2") (pintype "passive"))
      (node (ref "D2") (pin "A") (pinfunction "A_A") (pintype "passive"))
      (node (ref "J4") (pin "1") (pinfunction "VBUS_1") (pintype "passive"))
    )
    (net (code "81") (name "Net-(J6-RCT)") (class "Default")
      (node (ref "C27") (pin "1") (pinfunction "1_1") (pintype "passive"))
      (node (ref "J6") (pin "5") (pinfunction "RCT_5") (pintype "bidirectional"))
    )
    (net (code "82") (name "Net-(J6-TCT)") (class "Default")
      (node (ref "C26") (pin "1") (pinfunction "1_1") (pintype "passive"))
      (node (ref "J6") (pin "4") (pinfunction "TCT_4") (pintype "bidirectional"))
    )
    (net (code "83") (name "Net-(LED2-PadA)") (class "Default")
      (node (ref "LED2") (pin "A") (pinfunction "A_A") (pintype "passive"))
      (node (ref "RN1") (pin "1") (pinfunction "1_1") (pintype "passive"))
    )
    (net (code "84") (name "Net-(RN1B-1)") (class "Default")
      (node (ref "LED3") (pin "A") (pinfunction "A_A") (pintype "passive"))
      (node (ref "RN1") (pin "2") (pinfunction "1_2") (pintype "passive"))
    )
    (net (code "85") (name "Net-(RN1C-1)") (class "Default")
      (node (ref "LED4") (pin "A") (pinfunction "A_A") (pintype "passive"))
      (node (ref "RN1") (pin "3") (pinfunction "1_3") (pintype "passive"))
    )
    (net (code "86") (name "Net-(RN1D-1)") (class "Default")
      (node (ref "LED1") (pin "A") (pinfunction "A_A") (pintype "passive"))
      (node (ref "RN1") (pin "4") (pinfunction "1_4") (pintype "passive"))
    )
    (net (code "87") (name "VDD") (class "Default")
      (node (ref "C21") (pin "+") (pinfunction "+_+") (pintype "passive"))
      (node (ref "C22") (pin "1") (pinfunction "1_1") (pintype "passive"))
      (node (ref "C23") (pin "1") (pinfunction "1_1") (pintype "passive"))
      (node (ref "FL1") (pin "2") (pinfunction "2_2") (pintype "passive"))
      (node (ref "FL2") (pin "1") (pinfunction "1_1") (pintype "passive"))
      (node (ref "IC1") (pin "14") (pinfunction "DVDD33_14") (pintype "bidirectional"))
      (node (ref "J6") (pin "11") (pinfunction "GRN+_11") (pintype "bidirectional"))
      (node (ref "R10") (pin "2") (pinfunction "2_2") (pintype "passive"))
      (node (ref "R11") (pin "1") (pinfunction "1_1") (pintype "passive"))
      (node (ref "R12") (pin "2") (pinfunction "2_2") (pintype "passive"))
      (node (ref "R13") (pin "2") (pinfunction "2_2") (pintype "passive"))
    )
    (net (code "88") (name "unconnected-(IC1-COL-Pad27)") (class "Default")
      (node (ref "IC1") (pin "27") (pinfunction "COL_27") (pintype "bidirectional"))
    )
    (net (code "89") (name "unconnected-(IC1-RXC-Pad13)") (class "Default")
      (node (ref "IC1") (pin "13") (pinfunction "RXC_13") (pintype "bidirectional"))
    )
    (net (code "90") (name "unconnected-(IC1-RXD[3]{slash}CLK_CTL-Pad12)") (class "Default")
      (node (ref "IC1") (pin "12") (pinfunction "RXD[3]/CLK_CTL_12") (pintype "bidirectional"))
    )
    (net (code "91") (name "unconnected-(IC1-TXC-Pad15)") (class "Default")
      (node (ref "IC1") (pin "15") (pinfunction "TXC_15") (pintype "bidirectional"))
    )
    (net (code "92") (name "unconnected-(IC1-TXD[2]-Pad18)") (class "Default")
      (node (ref "IC1") (pin "18") (pinfunction "TXD[2]_18") (pintype "bidirectional"))
    )
    (net (code "93") (name "unconnected-(IC1-TXD[3]-Pad19)") (class "Default")
      (node (ref "IC1") (pin "19") (pinfunction "TXD[3]_19") (pintype "bidirectional"))
    )
    (net (code "94") (name "unconnected-(J5-Pad1)") (class "Default")
      (node (ref "J5") (pin "1") (pinfunction "1_1") (pintype "passive"))
    )
    (net (code "95") (name "unconnected-(J6-NC-Pad7)") (class "Default")
      (node (ref "J6") (pin "7") (pinfunction "NC_7") (pintype "bidirectional"))
    )
    (net (code "96") (name "unconnected-(RN2-Pad1)") (class "Default")
      (node (ref "RN2") (pin "1") (pinfunction "1_1") (pintype "passive"))
    )
    (net (code "97") (name "unconnected-(RN2A-2-Pad8)") (class "Default")
      (node (ref "RN2") (pin "8") (pinfunction "2_8") (pintype "passive"))
    )
    (net (code "98") (name "unconnected-(RN3-Pad1)") (class "Default")
      (node (ref "RN3") (pin "1") (pinfunction "1_1") (pintype "passive"))
    )
    (net (code "99") (name "unconnected-(RN3A-2-Pad8)") (class "Default")
      (node (ref "RN3") (pin "8") (pinfunction "2_8") (pintype "passive"))
    )
    (net (code "100") (name "unconnected-(U2-PA0{slash}WKUP-Pad14)") (class "Default")
      (node (ref "U2") (pin "14") (pinfunction "PA0/WKUP_14") (pintype "bidirectional"))
    )
    (net (code "101") (name "unconnected-(U2-PA3-Pad17)") (class "Default")
      (node (ref "U2") (pin "17") (pinfunction "PA3_17") (pintype "bidirectional"))
    )
    (net (code "102") (name "unconnected-(U3-P4-Pad4)") (class "Default")
      (node (ref "U3") (pin "4") (pinfunction "P4_4") (pintype "no_connect"))
    )
  )
)
